# Sheet1.net
KiCad netlist of a schematic drawn in Altium Designer
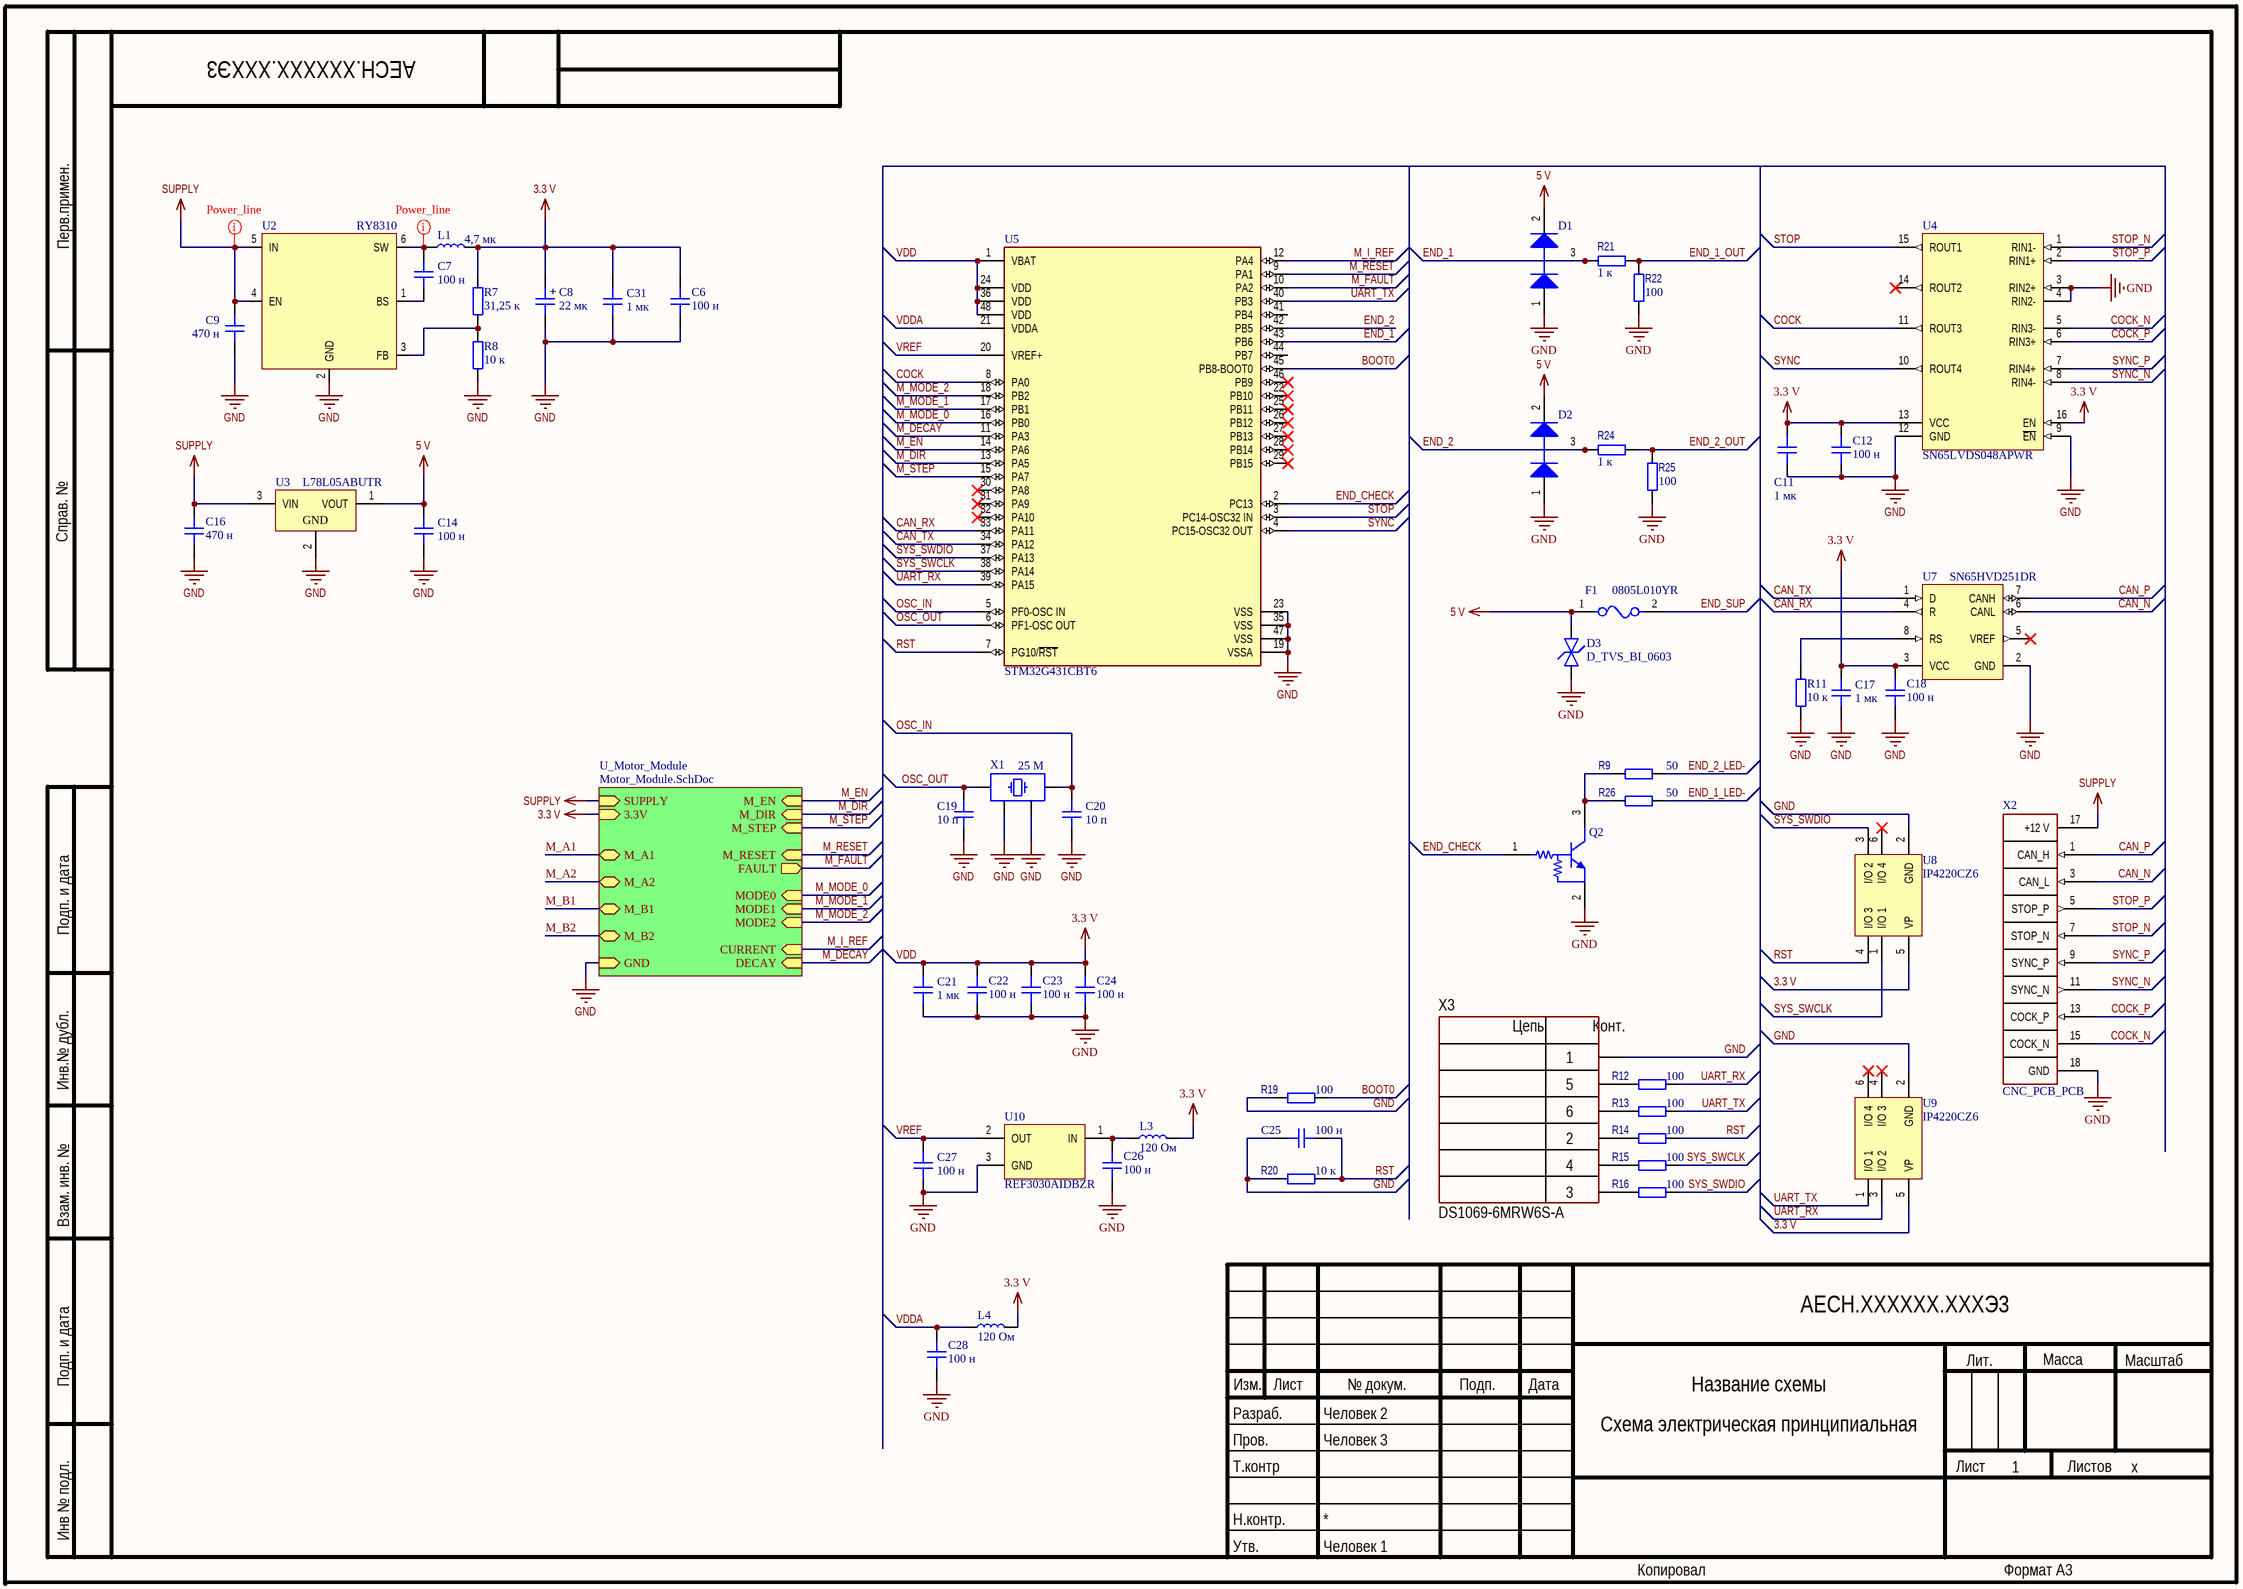
[diagram p0: Sheet1.SchDoc]

(export (version "E")
  (design (tool "Eeschema 10.0.6"))
  (components
    (comp (ref "C6")
      (value "100 н")
      (footprint "CAP_0603")
      (description "Керамический конденсатор")
      (libsource (lib "Schematic-Lib-PhilsLab") (part "CAP_0603"))
    )
    (comp (ref "C7")
      (value "100 н")
      (footprint "CAP_0603")
      (description "Керамический конденсатор")
      (libsource (lib "Schematic-Lib-PhilsLab") (part "CAP_0805"))
    )
    (comp (ref "C8")
      (value "22 мк")
      (footprint "TANTAL_B")
      (description "Танталовый конденсатор")
      (fields (field (name "VOLTAGE") "6,3"))
      (libsource (lib "Schematic-Lib-PhilsLab") (part "CAP_ALEL_16x16.5_25V"))
    )
    (comp (ref "C9")
      (value "470 н")
      (footprint "CAP_0805")
      (description "Capacitor SMD 0805")
      (fields (field (name "VOLTAGE") "50"))
      (libsource (lib "Schematic-Lib-PhilsLab") (part "CAP_0805"))
    )
    (comp (ref "C11")
      (value "1 мк")
      (footprint "CAP_0603")
      (description "Керамический конденсатор")
      (libsource (lib "Schematic-Lib-PhilsLab") (part "CAP_0603"))
    )
    (comp (ref "C12")
      (value "100 н")
      (footprint "CAP_0603")
      (description "Керамический конденсатор")
      (libsource (lib "Schematic-Lib-PhilsLab") (part "CAP_0603"))
    )
    (comp (ref "C14")
      (value "100 н")
      (footprint "CAP_0603")
      (description "Керамический конденсатор")
      (libsource (lib "Schematic-Lib-PhilsLab") (part "CAP_0805"))
    )
    (comp (ref "C16")
      (value "470 н")
      (footprint "CAP_0805")
      (description "Capacitor SMD 0805")
      (fields (field (name "VOLTAGE") "50"))
      (libsource (lib "Schematic-Lib-PhilsLab") (part "CAP_0805"))
    )
    (comp (ref "C17")
      (value "1 мк")
      (footprint "CAP_0603")
      (description "Керамический конденсатор")
      (libsource (lib "Schematic-Lib-PhilsLab") (part "CAP_0603"))
    )
    (comp (ref "C18")
      (value "100 н")
      (footprint "CAP_0603")
      (description "Керамический конденсатор")
      (libsource (lib "Schematic-Lib-PhilsLab") (part "CAP_0603"))
    )
    (comp (ref "C19")
      (value "10 п")
      (footprint "CAP_0603")
      (description "Керамический конденсатор")
      (libsource (lib "Schematic-Lib-PhilsLab") (part "CAP_0603"))
    )
    (comp (ref "C20")
      (value "10 п")
      (footprint "CAP_0603")
      (description "Керамический конденсатор")
      (libsource (lib "Schematic-Lib-PhilsLab") (part "CAP_0603"))
    )
    (comp (ref "C21")
      (value "1 мк")
      (footprint "CAP_0603")
      (description "Керамический конденсатор")
      (libsource (lib "Schematic-Lib-PhilsLab") (part "CAP_0603"))
    )
    (comp (ref "C22")
      (value "100 н")
      (footprint "CAP_0603")
      (description "Керамический конденсатор")
      (libsource (lib "Schematic-Lib-PhilsLab") (part "CAP_0603"))
    )
    (comp (ref "C23")
      (value "100 н")
      (footprint "CAP_0603")
      (description "Керамический конденсатор")
      (libsource (lib "Schematic-Lib-PhilsLab") (part "CAP_0603"))
    )
    (comp (ref "C24")
      (value "100 н")
      (footprint "CAP_0603")
      (description "Керамический конденсатор")
      (libsource (lib "Schematic-Lib-PhilsLab") (part "CAP_0603"))
    )
    (comp (ref "C25")
      (value "100 н")
      (footprint "CAP_0603")
      (description "Керамический конденсатор")
      (libsource (lib "Schematic-Lib-PhilsLab") (part "CAP_0603"))
    )
    (comp (ref "C26")
      (value "100 н")
      (footprint "CAP_0603")
      (description "Capacitor SMD 0603")
      (libsource (lib "Schematic-Lib-PhilsLab") (part "CAP_0603"))
    )
    (comp (ref "C27")
      (value "100 н")
      (footprint "CAP_0603")
      (description "Керамический конденсатор")
      (libsource (lib "Schematic-Lib-PhilsLab") (part "CAP_0603"))
    )
    (comp (ref "C28")
      (value "100 н")
      (footprint "CAP_0603")
      (description "Capacitor SMD 0603")
      (libsource (lib "Schematic-Lib-PhilsLab") (part "CAP_0603"))
    )
    (comp (ref "C31")
      (value "1 мк")
      (footprint "CAP_0603")
      (description "Керамический конденсатор")
      (libsource (lib "Schematic-Lib-PhilsLab") (part "CAP_0603"))
    )
    (comp (ref "D1")
      (value "BAT54AW")
      (footprint "ONSC-SOT-323-3-419-04_V")
      (description "Dual Series Schottky Barrier Diodes, 3-Pin SOT-323, Pb-Free, Tape and Reel")
      (libsource (lib "Altium Content Vault") (part "ONSC-D-A1K2C3-3"))
    )
    (comp (ref "D2")
      (value "BAT54AW")
      (footprint "ONSC-SOT-323-3-419-04_V")
      (description "Dual Series Schottky Barrier Diodes, 3-Pin SOT-323, Pb-Free, Tape and Reel")
      (libsource (lib "Altium Content Vault") (part "ONSC-D-A1K2C3-3"))
    )
    (comp (ref "D3")
      (value "D_TVS_BI_0603")
      (footprint "D_0603")
      (description "Diode TVS / ESD Bidirectional 0603")
      (libsource (lib "Schematic-Lib-PhilsLab") (part "D_TVS_BI_0603"))
    )
    (comp (ref "F1")
      (value "0805L010YR")
      (footprint "FP-0805L010-MFG")
      (libsource (lib "Altium Content Vault") (part "5bcf9b9f640e542cf0359d10258e979"))
    )
    (comp (ref "L1")
      (value "4,7 мк")
      (footprint "IND_1008")
      (description "Inductor SMD 1008")
      (libsource (lib "Schematic-Lib-PhilsLab") (part "IND_1008"))
    )
    (comp (ref "L3")
      (value "120 Ом")
      (footprint "IND_0603")
      (description "Inductor SMD 0603")
      (libsource (lib "Schematic-Lib-PhilsLab") (part "IND_0603"))
    )
    (comp (ref "L4")
      (value "120 Ом")
      (footprint "IND_0603")
      (description "Inductor SMD 0603")
      (libsource (lib "Schematic-Lib-PhilsLab") (part "IND_0603"))
    )
    (comp (ref "Q2")
      (value "MMUN2233LT1G")
      (footprint "ONSC-SOT-23-3-318-08_V")
      (libsource (lib "Altium Content Vault") (part "ONSC-BRT-NPN-B1E2C3-3"))
    )
    (comp (ref "R7")
      (value "31,25 к")
      (footprint "RES_0603")
      (description "Резистор")
      (libsource (lib "Schematic-Lib-PhilsLab") (part "RES_0805"))
    )
    (comp (ref "R8")
      (value "10 к")
      (footprint "RES_0603")
      (description "Резистор")
      (libsource (lib "Schematic-Lib-PhilsLab") (part "RES_0805"))
    )
    (comp (ref "R9")
      (value "50")
      (footprint "RES_0603")
      (description "Резистор")
      (libsource (lib "Schematic-Lib-PhilsLab") (part "RES_0603"))
    )
    (comp (ref "R11")
      (value "10 к")
      (footprint "RES_0603")
      (description "Резистор")
      (libsource (lib "Schematic-Lib-PhilsLab") (part "RES_0603"))
    )
    (comp (ref "R12")
      (value "100")
      (footprint "RES_0603")
      (description "Резистор")
      (libsource (lib "Schematic-Lib-PhilsLab") (part "RES_0603"))
    )
    (comp (ref "R13")
      (value "100")
      (footprint "RES_0603")
      (description "Резистор")
      (libsource (lib "Schematic-Lib-PhilsLab") (part "RES_0603"))
    )
    (comp (ref "R14")
      (value "100")
      (footprint "RES_0603")
      (description "Резистор")
      (libsource (lib "Schematic-Lib-PhilsLab") (part "RES_0603"))
    )
    (comp (ref "R15")
      (value "100")
      (footprint "RES_0603")
      (description "Резистор")
      (libsource (lib "Schematic-Lib-PhilsLab") (part "RES_0603"))
    )
    (comp (ref "R16")
      (value "100")
      (footprint "RES_0603")
      (description "Резистор")
      (libsource (lib "Schematic-Lib-PhilsLab") (part "RES_0603"))
    )
    (comp (ref "R19")
      (value "100")
      (footprint "RES_0603")
      (description "Резистор")
      (libsource (lib "Schematic-Lib-PhilsLab") (part "RES_0603"))
    )
    (comp (ref "R20")
      (value "10 к")
      (footprint "RES_0603")
      (description "Резистор")
      (libsource (lib "Schematic-Lib-PhilsLab") (part "RES_0603"))
    )
    (comp (ref "R21")
      (value "1 к")
      (footprint "RES_0603")
      (description "Резистор")
      (libsource (lib "Schematic-Lib-PhilsLab") (part "RES_0603"))
    )
    (comp (ref "R22")
      (value "100")
      (footprint "RES_0603")
      (description "Резистор")
      (libsource (lib "Schematic-Lib-PhilsLab") (part "RES_0603"))
    )
    (comp (ref "R24")
      (value "1 к")
      (footprint "RES_0603")
      (description "Резистор")
      (libsource (lib "Schematic-Lib-PhilsLab") (part "RES_0603"))
    )
    (comp (ref "R25")
      (value "100")
      (footprint "RES_0603")
      (description "Резистор")
      (libsource (lib "Schematic-Lib-PhilsLab") (part "RES_0603"))
    )
    (comp (ref "R26")
      (value "50")
      (footprint "RES_0603")
      (description "Резистор")
      (libsource (lib "Schematic-Lib-PhilsLab") (part "RES_0603"))
    )
    (comp (ref "U2")
      (value "RY8310")
      (footprint "SOT-23-6")
      (description "Понижающий DC-DC")
      (libsource (lib "Schematic-Lib-PhilsLab") (part "MT2492"))
    )
    (comp (ref "U3")
      (value "L78L05ABUTR")
      (footprint "SOT-89_N")
      (description "Positive Voltage Regulator, 5V, 4-Pin SOT-89, Tape and Reel")
      (libsource (lib "Altium Content Vault") (part "PM-REG-7805-SIL3"))
    )
    (comp (ref "U4")
      (value "SN65LVDS048APWR")
      (footprint "MTC16_M")
      (description "Драйвер LVDS")
      (libsource (lib "Altium Content Vault") (part "IN-LNDRV-DS90LV047ATM"))
    )
    (comp (ref "U5")
      (value "STM32G431CBT6")
      (footprint "FP-LQFP48-5B-MFG")
      (description "MAINSTREAM ARM CORTEX-M4+ MCU 17")
      (libsource (lib "Altium Content Vault") (part "08b09c1d51ec08ade740842f2b8671b"))
    )
    (comp (ref "U7")
      (value "SN65HVD251DR")
      (footprint "D0008A_N")
      (description "Драйвер CAN")
      (libsource (lib "Altium Content Vault") (part "TI-SN65HVD251-SOIC_D-8"))
    )
    (comp (ref "U8")
      (value "IP4220CZ6")
      (footprint "NXP-SOT457_L")
      (description "Сборка защитных диодов")
      (libsource (lib "Altium Content Vault") (part "NXP-IP4220CZ6-6"))
    )
    (comp (ref "U9")
      (value "IP4220CZ6")
      (footprint "NXP-SOT457_L")
      (description "Сборка защитных диодов")
      (libsource (lib "") (part "NXP-IP4220CZ6-6_1"))
    )
    (comp (ref "U10")
      (value "REF3030AIDBZR")
      (footprint "DBZ0003A_N")
      (libsource (lib "Altium Content Vault") (part "TI-REF3020DBZ3"))
    )
    (comp (ref "X1")
      (value "25 M")
      (footprint "XTAL_3225")
      (description "Кварцевый резонатор")
      (libsource (lib "Schematic-Lib-PhilsLab") (part "TSX-3225_24.0000MF15X-AC"))
    )
    (comp (ref "X2")
      (value "CNC_PCB_PCB")
      (footprint "CNC_PCB_PCB")
      (libsource (lib "BarkockLib") (part "CNC_PCB_PCB"))
    )
    (comp (ref "X3")
      (value "DS1069-6MRW6S-A")
      (footprint "CON: CWF-6R")
      (libsource (lib "Connectors") (part "6-Connector"))
    )
  )
  (nets
    (net (code "1") (name "/BOOT0") (class "Default")
      (node (ref "R19") (pin "1") (pinfunction "1_1") (pintype "passive"))
      (node (ref "U5") (pin "45") (pinfunction "PB8-BOOT0_45") (pintype "bidirectional"))
    )
    (net (code "2") (name "/CAN_N") (class "Default")
      (node (ref "U7") (pin "6") (pinfunction "CANL_6") (pintype "bidirectional"))
      (node (ref "X2") (pin "3") (pinfunction "CAN_L_3") (pintype "input"))
    )
    (net (code "3") (name "/CAN_P") (class "Default")
      (node (ref "U7") (pin "7") (pinfunction "CANH_7") (pintype "bidirectional"))
      (node (ref "X2") (pin "1") (pinfunction "CAN_H_1") (pintype "input"))
    )
    (net (code "4") (name "/CAN_RX") (class "Default")
      (node (ref "U5") (pin "33") (pinfunction "PA11_33") (pintype "bidirectional"))
      (node (ref "U7") (pin "4") (pinfunction "R_4") (pintype "output"))
    )
    (net (code "5") (name "/CAN_TX") (class "Default")
      (node (ref "U5") (pin "34") (pinfunction "PA12_34") (pintype "bidirectional"))
      (node (ref "U7") (pin "1") (pinfunction "D_1") (pintype "input"))
    )
    (net (code "6") (name "/COCK") (class "Default")
      (node (ref "U4") (pin "11") (pinfunction "ROUT3_11") (pintype "output"))
      (node (ref "U5") (pin "8") (pinfunction "PA0_8") (pintype "bidirectional"))
    )
    (net (code "7") (name "/COCK_N") (class "Default")
      (node (ref "U4") (pin "5") (pinfunction "RIN3-_5") (pintype "power_in"))
      (node (ref "X2") (pin "15") (pinfunction "COCK_N_15") (pintype "power_in"))
    )
    (net (code "8") (name "/COCK_P") (class "Default")
      (node (ref "U4") (pin "6") (pinfunction "RIN3+_6") (pintype "input"))
      (node (ref "X2") (pin "13") (pinfunction "COCK_P_13") (pintype "input"))
    )
    (net (code "9") (name "/END_1") (class "Default")
      (node (ref "D1") (pin "3") (pinfunction "K/A_3") (pintype "passive"))
      (node (ref "R21") (pin "2") (pinfunction "2_2") (pintype "passive"))
      (node (ref "U5") (pin "43") (pinfunction "PB6_43") (pintype "bidirectional"))
    )
    (net (code "10") (name "/END_1_LED-") (class "Default")
      (node (ref "R26") (pin "2") (pinfunction "2_2") (pintype "passive"))
    )
    (net (code "11") (name "/END_1_OUT") (class "Default")
      (node (ref "R21") (pin "1") (pinfunction "1_1") (pintype "passive"))
      (node (ref "R22") (pin "1") (pinfunction "1_1") (pintype "passive"))
    )
    (net (code "12") (name "/END_2") (class "Default")
      (node (ref "D2") (pin "3") (pinfunction "K/A_3") (pintype "passive"))
      (node (ref "R24") (pin "2") (pinfunction "2_2") (pintype "passive"))
      (node (ref "U5") (pin "42") (pinfunction "PB5_42") (pintype "bidirectional"))
    )
    (net (code "13") (name "/END_2_LED-") (class "Default")
      (node (ref "R9") (pin "2") (pinfunction "2_2") (pintype "passive"))
    )
    (net (code "14") (name "/END_2_OUT") (class "Default")
      (node (ref "R24") (pin "1") (pinfunction "1_1") (pintype "passive"))
      (node (ref "R25") (pin "1") (pinfunction "1_1") (pintype "passive"))
    )
    (net (code "15") (name "/END_CHECK") (class "Default")
      (node (ref "Q2") (pin "1") (pinfunction "B_1") (pintype "passive"))
      (node (ref "U5") (pin "2") (pinfunction "PC13_2") (pintype "bidirectional"))
    )
    (net (code "16") (name "/END_SUP") (class "Default")
      (node (ref "F1") (pin "2") (pinfunction "2_2") (pintype "passive"))
    )
    (net (code "21") (name "/M_DECAY") (class "Default")
      (node (ref "U5") (pin "11") (pinfunction "PA3_11") (pintype "bidirectional"))
    )
    (net (code "22") (name "/M_DIR") (class "Default")
      (node (ref "U5") (pin "13") (pinfunction "PA5_13") (pintype "bidirectional"))
    )
    (net (code "23") (name "/M_EN") (class "Default")
      (node (ref "U5") (pin "14") (pinfunction "PA6_14") (pintype "bidirectional"))
    )
    (net (code "24") (name "/M_FAULT") (class "Default")
      (node (ref "U5") (pin "10") (pinfunction "PA2_10") (pintype "bidirectional"))
    )
    (net (code "25") (name "/M_I_REF") (class "Default")
      (node (ref "U5") (pin "12") (pinfunction "PA4_12") (pintype "bidirectional"))
    )
    (net (code "26") (name "/M_MODE_0") (class "Default")
      (node (ref "U5") (pin "16") (pinfunction "PB0_16") (pintype "bidirectional"))
    )
    (net (code "27") (name "/M_MODE_1") (class "Default")
      (node (ref "U5") (pin "17") (pinfunction "PB1_17") (pintype "bidirectional"))
    )
    (net (code "28") (name "/M_MODE_2") (class "Default")
      (node (ref "U5") (pin "18") (pinfunction "PB2_18") (pintype "bidirectional"))
    )
    (net (code "29") (name "/M_RESET") (class "Default")
      (node (ref "U5") (pin "9") (pinfunction "PA1_9") (pintype "bidirectional"))
    )
    (net (code "30") (name "/M_STEP") (class "Default")
      (node (ref "U5") (pin "15") (pinfunction "PA7_15") (pintype "bidirectional"))
    )
    (net (code "31") (name "/OSC_IN") (class "Default")
      (node (ref "C20") (pin "1") (pinfunction "1_1") (pintype "passive"))
      (node (ref "U5") (pin "5") (pinfunction "PF0-OSC_IN_5") (pintype "bidirectional"))
      (node (ref "X1") (pin "3") (pinfunction "3_3") (pintype "passive"))
    )
    (net (code "32") (name "/OSC_OUT") (class "Default")
      (node (ref "C19") (pin "1") (pinfunction "1_1") (pintype "passive"))
      (node (ref "U5") (pin "6") (pinfunction "PF1-OSC_OUT_6") (pintype "bidirectional"))
      (node (ref "X1") (pin "1") (pinfunction "1_1") (pintype "passive"))
    )
    (net (code "33") (name "/RST") (class "Default")
      (node (ref "C25") (pin "2") (pinfunction "2_2") (pintype "passive"))
      (node (ref "R14") (pin "1") (pinfunction "1_1") (pintype "passive"))
      (node (ref "R20") (pin "1") (pinfunction "1_1") (pintype "passive"))
      (node (ref "U5") (pin "7") (pinfunction "PG10/~{RST}_7") (pintype "bidirectional"))
      (node (ref "U8") (pin "4") (pinfunction "I/O_3_4") (pintype "passive"))
    )
    (net (code "34") (name "/STOP") (class "Default")
      (node (ref "U4") (pin "15") (pinfunction "ROUT1_15") (pintype "output"))
      (node (ref "U5") (pin "3") (pinfunction "PC14-OSC32_IN_3") (pintype "bidirectional"))
    )
    (net (code "35") (name "/STOP_N") (class "Default")
      (node (ref "U4") (pin "1") (pinfunction "RIN1-_1") (pintype "input"))
      (node (ref "X2") (pin "7") (pinfunction "STOP_N_7") (pintype "input"))
    )
    (net (code "36") (name "/STOP_P") (class "Default")
      (node (ref "U4") (pin "2") (pinfunction "RIN1+_2") (pintype "input"))
      (node (ref "X2") (pin "5") (pinfunction "STOP_P_5") (pintype "output"))
    )
    (net (code "37") (name "/SYNC") (class "Default")
      (node (ref "U4") (pin "10") (pinfunction "ROUT4_10") (pintype "output"))
      (node (ref "U5") (pin "4") (pinfunction "PC15-OSC32_OUT_4") (pintype "bidirectional"))
    )
    (net (code "38") (name "/SYNC_N") (class "Default")
      (node (ref "U4") (pin "8") (pinfunction "RIN4-_8") (pintype "input"))
      (node (ref "X2") (pin "11") (pinfunction "SYNC_N_11") (pintype "output"))
    )
    (net (code "39") (name "/SYNC_P") (class "Default")
      (node (ref "U4") (pin "7") (pinfunction "RIN4+_7") (pintype "input"))
      (node (ref "X2") (pin "9") (pinfunction "SYNC_P_9") (pintype "input"))
    )
    (net (code "40") (name "/SYS_SWCLK") (class "Default")
      (node (ref "R15") (pin "1") (pinfunction "1_1") (pintype "passive"))
      (node (ref "U5") (pin "38") (pinfunction "PA14_38") (pintype "bidirectional"))
      (node (ref "U8") (pin "1") (pinfunction "I/O_1_1") (pintype "passive"))
    )
    (net (code "41") (name "/SYS_SWDIO") (class "Default")
      (node (ref "R16") (pin "1") (pinfunction "1_1") (pintype "passive"))
      (node (ref "U5") (pin "37") (pinfunction "PA13_37") (pintype "bidirectional"))
      (node (ref "U8") (pin "3") (pinfunction "I/O_2_3") (pintype "passive"))
    )
    (net (code "42") (name "/UART_RX") (class "Default")
      (node (ref "R12") (pin "1") (pinfunction "1_1") (pintype "passive"))
      (node (ref "U5") (pin "39") (pinfunction "PA15_39") (pintype "bidirectional"))
      (node (ref "U9") (pin "3") (pinfunction "I/O_2_3") (pintype "passive"))
    )
    (net (code "43") (name "/UART_TX") (class "Default")
      (node (ref "R13") (pin "1") (pinfunction "1_1") (pintype "passive"))
      (node (ref "U5") (pin "40") (pinfunction "PB3_40") (pintype "bidirectional"))
      (node (ref "U9") (pin "1") (pinfunction "I/O_1_1") (pintype "passive"))
    )
    (net (code "44") (name "/VDDA") (class "Default")
      (node (ref "C28") (pin "1") (pinfunction "1_1") (pintype "passive"))
      (node (ref "L4") (pin "1") (pinfunction "1_1") (pintype "passive"))
      (node (ref "U5") (pin "21") (pinfunction "VDDA_21") (pintype "power_in"))
    )
    (net (code "45") (name "/VREF") (class "Default")
      (node (ref "C27") (pin "2") (pinfunction "2_2") (pintype "passive"))
      (node (ref "U10") (pin "2") (pinfunction "OUT_2") (pintype "power_in"))
      (node (ref "U5") (pin "20") (pinfunction "VREF+_20") (pintype "power_in"))
    )
    (net (code "46") (name "3.3 V") (class "Default")
      (node (ref "C11") (pin "2") (pinfunction "2_2") (pintype "passive"))
      (node (ref "C12") (pin "2") (pinfunction "2_2") (pintype "passive"))
      (node (ref "C17") (pin "2") (pinfunction "2_2") (pintype "passive"))
      (node (ref "C18") (pin "1") (pinfunction "1_1") (pintype "passive"))
      (node (ref "C21") (pin "2") (pinfunction "2_2") (pintype "passive"))
      (node (ref "C22") (pin "1") (pinfunction "1_1") (pintype "passive"))
      (node (ref "C23") (pin "1") (pinfunction "1_1") (pintype "passive"))
      (node (ref "C24") (pin "1") (pinfunction "1_1") (pintype "passive"))
      (node (ref "C31") (pin "2") (pinfunction "2_2") (pintype "passive"))
      (node (ref "C6") (pin "1") (pinfunction "1_1") (pintype "passive"))
      (node (ref "C8") (pin "1") (pinfunction "1_1") (pintype "passive"))
      (node (ref "L1") (pin "2") (pinfunction "2_2") (pintype "passive"))
      (node (ref "L3") (pin "2") (pinfunction "2_2") (pintype "passive"))
      (node (ref "L4") (pin "2") (pinfunction "2_2") (pintype "passive"))
      (node (ref "R7") (pin "1") (pinfunction "1_1") (pintype "passive"))
      (node (ref "U4") (pin "13") (pinfunction "VCC_13") (pintype "power_in"))
      (node (ref "U4") (pin "16") (pinfunction "EN_16") (pintype "input"))
      (node (ref "U5") (pin "1") (pinfunction "VBAT_1") (pintype "power_in"))
      (node (ref "U5") (pin "24") (pinfunction "VDD_24") (pintype "power_in"))
      (node (ref "U5") (pin "36") (pinfunction "VDD_36") (pintype "power_in"))
      (node (ref "U5") (pin "48") (pinfunction "VDD_48") (pintype "power_in"))
      (node (ref "U7") (pin "3") (pinfunction "VCC_3") (pintype "power_in"))
      (node (ref "U8") (pin "5") (pinfunction "VP_5") (pintype "power_in"))
      (node (ref "U9") (pin "5") (pinfunction "VP_5") (pintype "power_in"))
    )
    (net (code "47") (name "5 V") (class "Default")
      (node (ref "C14") (pin "2") (pinfunction "2_2") (pintype "passive"))
      (node (ref "D1") (pin "2") (pinfunction "K_2") (pintype "passive"))
      (node (ref "D2") (pin "2") (pinfunction "K_2") (pintype "passive"))
      (node (ref "D3") (pin "K") (pinfunction "K_K") (pintype "passive"))
      (node (ref "F1") (pin "1") (pinfunction "1_1") (pintype "passive"))
      (node (ref "U3") (pin "1") (pinfunction "VOUT_1") (pintype "power_in"))
    )
    (net (code "48") (name "GND") (class "Default")
      (node (ref "C11") (pin "1") (pinfunction "1_1") (pintype "passive"))
      (node (ref "C12") (pin "1") (pinfunction "1_1") (pintype "passive"))
      (node (ref "C14") (pin "1") (pinfunction "1_1") (pintype "passive"))
      (node (ref "C16") (pin "2") (pinfunction "2_2") (pintype "passive"))
      (node (ref "C17") (pin "1") (pinfunction "1_1") (pintype "passive"))
      (node (ref "C18") (pin "2") (pinfunction "2_2") (pintype "passive"))
      (node (ref "C19") (pin "2") (pinfunction "2_2") (pintype "passive"))
      (node (ref "C20") (pin "2") (pinfunction "2_2") (pintype "passive"))
      (node (ref "C21") (pin "1") (pinfunction "1_1") (pintype "passive"))
      (node (ref "C22") (pin "2") (pinfunction "2_2") (pintype "passive"))
      (node (ref "C23") (pin "2") (pinfunction "2_2") (pintype "passive"))
      (node (ref "C24") (pin "2") (pinfunction "2_2") (pintype "passive"))
      (node (ref "C25") (pin "1") (pinfunction "1_1") (pintype "passive"))
      (node (ref "C26") (pin "2") (pinfunction "2_2") (pintype "passive"))
      (node (ref "C27") (pin "1") (pinfunction "1_1") (pintype "passive"))
      (node (ref "C28") (pin "2") (pinfunction "2_2") (pintype "passive"))
      (node (ref "C31") (pin "1") (pinfunction "1_1") (pintype "passive"))
      (node (ref "C6") (pin "2") (pinfunction "2_2") (pintype "passive"))
      (node (ref "C8") (pin "2") (pinfunction "2_2") (pintype "passive"))
      (node (ref "C9") (pin "2") (pinfunction "2_2") (pintype "passive"))
      (node (ref "D1") (pin "1") (pinfunction "A_1") (pintype "passive"))
      (node (ref "D2") (pin "1") (pinfunction "A_1") (pintype "passive"))
      (node (ref "D3") (pin "A") (pinfunction "A_A") (pintype "passive"))
      (node (ref "Q2") (pin "2") (pinfunction "E_2") (pintype "passive"))
      (node (ref "R11") (pin "1") (pinfunction "1_1") (pintype "passive"))
      (node (ref "R19") (pin "2") (pinfunction "2_2") (pintype "passive"))
      (node (ref "R20") (pin "2") (pinfunction "2_2") (pintype "passive"))
      (node (ref "R22") (pin "2") (pinfunction "2_2") (pintype "passive"))
      (node (ref "R25") (pin "2") (pinfunction "2_2") (pintype "passive"))
      (node (ref "R8") (pin "2") (pinfunction "2_2") (pintype "passive"))
      (node (ref "U10") (pin "3") (pinfunction "GND_3") (pintype "power_in"))
      (node (ref "U2") (pin "2") (pinfunction "GND_2") (pintype "passive"))
      (node (ref "U3") (pin "2") (pinfunction "GND_2") (pintype "power_in"))
      (node (ref "U4") (pin "12") (pinfunction "GND_12") (pintype "power_in"))
      (node (ref "U4") (pin "3") (pinfunction "RIN2+_3") (pintype "input"))
      (node (ref "U4") (pin "4") (pinfunction "RIN2-_4") (pintype "power_in"))
      (node (ref "U4") (pin "9") (pinfunction "~{EN}_9") (pintype "input"))
      (node (ref "U5") (pin "19") (pinfunction "VSSA_19") (pintype "power_in"))
      (node (ref "U5") (pin "23") (pinfunction "VSS_23") (pintype "power_in"))
      (node (ref "U5") (pin "35") (pinfunction "VSS_35") (pintype "power_in"))
      (node (ref "U5") (pin "47") (pinfunction "VSS_47") (pintype "power_in"))
      (node (ref "U7") (pin "2") (pinfunction "GND_2") (pintype "power_in"))
      (node (ref "U8") (pin "2") (pinfunction "GND_2") (pintype "power_in"))
      (node (ref "U9") (pin "2") (pinfunction "GND_2") (pintype "power_in"))
      (node (ref "X1") (pin "2") (pinfunction "2_2") (pintype "passive"))
      (node (ref "X1") (pin "4") (pinfunction "4_4") (pintype "passive"))
      (node (ref "X2") (pin "18") (pinfunction "GND_18") (pintype "power_in"))
      (node (ref "X3") (pin "1") (pinfunction "1_1") (pintype "passive"))
    )
    (net (code "49") (name "Net-(Q2-C)") (class "Default")
      (node (ref "Q2") (pin "3") (pinfunction "C_3") (pintype "passive"))
      (node (ref "R26") (pin "1") (pinfunction "1_1") (pintype "passive"))
      (node (ref "R9") (pin "1") (pinfunction "1_1") (pintype "passive"))
    )
    (net (code "50") (name "Net-(R12-Pad2)") (class "Default")
      (node (ref "R12") (pin "2") (pinfunction "2_2") (pintype "passive"))
      (node (ref "X3") (pin "5") (pinfunction "5_5") (pintype "passive"))
    )
    (net (code "51") (name "Net-(R13-Pad2)") (class "Default")
      (node (ref "R13") (pin "2") (pinfunction "2_2") (pintype "passive"))
      (node (ref "X3") (pin "6") (pinfunction "6_6") (pintype "power_in"))
    )
    (net (code "52") (name "Net-(R14-Pad2)") (class "Default")
      (node (ref "R14") (pin "2") (pinfunction "2_2") (pintype "passive"))
      (node (ref "X3") (pin "2") (pinfunction "2_2") (pintype "power_in"))
    )
    (net (code "53") (name "Net-(R15-Pad2)") (class "Default")
      (node (ref "R15") (pin "2") (pinfunction "2_2") (pintype "passive"))
      (node (ref "X3") (pin "4") (pinfunction "4_4") (pintype "power_in"))
    )
    (net (code "54") (name "Net-(R16-Pad2)") (class "Default")
      (node (ref "R16") (pin "2") (pinfunction "2_2") (pintype "passive"))
      (node (ref "X3") (pin "3") (pinfunction "3_3") (pintype "power_in"))
    )
    (net (code "55") (name "Net-(U2-BS)") (class "Default")
      (node (ref "C7") (pin "1") (pinfunction "1_1") (pintype "passive"))
      (node (ref "U2") (pin "1") (pinfunction "BS_1") (pintype "passive"))
    )
    (net (code "56") (name "Net-(U2-FB)") (class "Default")
      (node (ref "R7") (pin "2") (pinfunction "2_2") (pintype "passive"))
      (node (ref "R8") (pin "1") (pinfunction "1_1") (pintype "passive"))
      (node (ref "U2") (pin "3") (pinfunction "FB_3") (pintype "passive"))
    )
    (net (code "57") (name "Net-(U2-SW)") (class "Default")
      (node (ref "C7") (pin "2") (pinfunction "2_2") (pintype "passive"))
      (node (ref "L1") (pin "1") (pinfunction "1_1") (pintype "passive"))
      (node (ref "U2") (pin "6") (pinfunction "SW_6") (pintype "passive"))
    )
    (net (code "58") (name "Net-(U7-RS)") (class "Default")
      (node (ref "R11") (pin "2") (pinfunction "2_2") (pintype "passive"))
      (node (ref "U7") (pin "8") (pinfunction "RS_8") (pintype "input"))
    )
    (net (code "59") (name "Net-(U10-IN)") (class "Default")
      (node (ref "C26") (pin "1") (pinfunction "1_1") (pintype "passive"))
      (node (ref "L3") (pin "1") (pinfunction "1_1") (pintype "passive"))
      (node (ref "U10") (pin "1") (pinfunction "IN_1") (pintype "power_in"))
    )
    (net (code "60") (name "SUPPLY") (class "Default")
      (node (ref "C16") (pin "1") (pinfunction "1_1") (pintype "passive"))
      (node (ref "C9") (pin "1") (pinfunction "1_1") (pintype "passive"))
      (node (ref "U2") (pin "4") (pinfunction "EN_4") (pintype "passive"))
      (node (ref "U2") (pin "5") (pinfunction "IN_5") (pintype "passive"))
      (node (ref "U3") (pin "3") (pinfunction "VIN_3") (pintype "power_in"))
      (node (ref "X2") (pin "17") (pinfunction "+12_V_17") (pintype "power_in"))
    )
    (net (code "61") (name "unconnected-(U4-ROUT2-Pad14)") (class "Default")
      (node (ref "U4") (pin "14") (pinfunction "ROUT2_14") (pintype "output+no_connect"))
    )
    (net (code "62") (name "unconnected-(U5-PA8-Pad30)") (class "Default")
      (node (ref "U5") (pin "30") (pinfunction "PA8_30") (pintype "bidirectional+no_connect"))
    )
    (net (code "63") (name "unconnected-(U5-PA9-Pad31)") (class "Default")
      (node (ref "U5") (pin "31") (pinfunction "PA9_31") (pintype "bidirectional+no_connect"))
    )
    (net (code "64") (name "unconnected-(U5-PA10-Pad32)") (class "Default")
      (node (ref "U5") (pin "32") (pinfunction "PA10_32") (pintype "bidirectional+no_connect"))
    )
    (net (code "65") (name "unconnected-(U5-PB4-Pad41)") (class "Default")
      (node (ref "U5") (pin "41") (pinfunction "PB4_41") (pintype "bidirectional"))
    )
    (net (code "66") (name "unconnected-(U5-PB7-Pad44)") (class "Default")
      (node (ref "U5") (pin "44") (pinfunction "PB7_44") (pintype "bidirectional"))
    )
    (net (code "67") (name "unconnected-(U5-PB9-Pad46)") (class "Default")
      (node (ref "U5") (pin "46") (pinfunction "PB9_46") (pintype "bidirectional+no_connect"))
    )
    (net (code "68") (name "unconnected-(U5-PB10-Pad22)") (class "Default")
      (node (ref "U5") (pin "22") (pinfunction "PB10_22") (pintype "bidirectional+no_connect"))
    )
    (net (code "69") (name "unconnected-(U5-PB11-Pad25)") (class "Default")
      (node (ref "U5") (pin "25") (pinfunction "PB11_25") (pintype "bidirectional+no_connect"))
    )
    (net (code "70") (name "unconnected-(U5-PB12-Pad26)") (class "Default")
      (node (ref "U5") (pin "26") (pinfunction "PB12_26") (pintype "bidirectional+no_connect"))
    )
    (net (code "71") (name "unconnected-(U5-PB13-Pad27)") (class "Default")
      (node (ref "U5") (pin "27") (pinfunction "PB13_27") (pintype "bidirectional+no_connect"))
    )
    (net (code "72") (name "unconnected-(U5-PB14-Pad28)") (class "Default")
      (node (ref "U5") (pin "28") (pinfunction "PB14_28") (pintype "bidirectional+no_connect"))
    )
    (net (code "73") (name "unconnected-(U5-PB15-Pad29)") (class "Default")
      (node (ref "U5") (pin "29") (pinfunction "PB15_29") (pintype "bidirectional+no_connect"))
    )
    (net (code "74") (name "unconnected-(U7-VREF-Pad5)") (class "Default")
      (node (ref "U7") (pin "5") (pinfunction "VREF_5") (pintype "output+no_connect"))
    )
    (net (code "75") (name "unconnected-(U8-I{slash}O_4-Pad6)") (class "Default")
      (node (ref "U8") (pin "6") (pinfunction "I/O_4_6") (pintype "passive+no_connect"))
    )
    (net (code "76") (name "unconnected-(U9-I{slash}O_3-Pad4)") (class "Default")
      (node (ref "U9") (pin "4") (pinfunction "I/O_3_4") (pintype "passive+no_connect"))
    )
    (net (code "77") (name "unconnected-(U9-I{slash}O_4-Pad6)") (class "Default")
      (node (ref "U9") (pin "6") (pinfunction "I/O_4_6") (pintype "passive+no_connect"))
    )
  )
)
